# Temp_and_Humi_SHTC3.net
KiCad netlist of a schematic drawn in Altium Designer
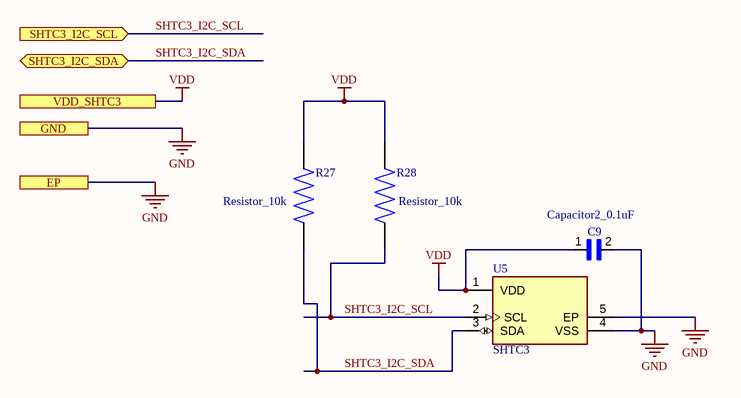
[diagram p0: Temp_and_Humi_SHTC3.SchDoc]

(export (version "E")
  (design (tool "Eeschema 10.0.6"))
  (components
    (comp (ref "C9")
      (value "Capacitor2_0.1uF")
      (footprint "Capacitor2_0.1uF")
      (description "Cap Ceramic 0.1uF 16V X5R 10% SMD 0402 85°C Paper T/R")
      (fields
        (field (name "MANUFACTURER") "KEMET")
        (field (name "MANUFACTURER PART NUMBER") "C0402C104K4PACTU")
      )
      (libsource (lib "Schematic_Lib") (part "Capacitor2_0.1uF"))
    )
    (comp (ref "R27")
      (value "Resistor_10k")
      (footprint "Resistor_10k")
      (description "Res Thin Film 0805 10K Ohm 1% 1/10W ±50ppm/°C Molded SMD SMD Paper T/R")
      (fields
        (field (name "MANUFACTURER") "TE Connectivity Neohm")
        (field (name "MANUFACTURER PART NUMBER") "CPF0805F10KC1")
      )
      (libsource (lib "Schematic_Lib") (part "Resistor_10k"))
    )
    (comp (ref "R28")
      (value "Resistor_10k")
      (footprint "Resistor_10k")
      (description "Res Thin Film 0805 10K Ohm 1% 1/10W ±50ppm/°C Molded SMD SMD Paper T/R")
      (fields
        (field (name "MANUFACTURER") "TE Connectivity Neohm")
        (field (name "MANUFACTURER PART NUMBER") "CPF0805F10KC1")
      )
      (libsource (lib "Schematic_Lib") (part "Resistor_10k"))
    )
    (comp (ref "U5")
      (value "SHTC3")
      (footprint "FP-SHTC3-MFG")
      (description "SENSOR HUMI/TEMP I2C 2% SMD")
      (fields
        (field (name "MANUFACTURER") "Sensirion")
        (field (name "OCTOPART") "https://octopart.com/shtc3-sensirion-91912225")
      )
      (libsource (lib "Altium Content Vault") (part "92e21da4ceb1e434b50171ab113565b"))
    )
  )
  (nets
    (net (code "1") (name "/SHTC3_I2C_SCL") (class "Default")
      (node (ref "R28") (pin "1") (pinfunction "1_1") (pintype "passive"))
      (node (ref "U5") (pin "2") (pinfunction "SCL_2") (pintype "input"))
    )
    (net (code "2") (name "/SHTC3_I2C_SDA") (class "Default")
      (node (ref "R27") (pin "1") (pinfunction "1_1") (pintype "passive"))
      (node (ref "U5") (pin "3") (pinfunction "SDA_3") (pintype "bidirectional"))
    )
    (net (code "3") (name "GND") (class "Default")
      (node (ref "C9") (pin "2") (pinfunction "2_2") (pintype "passive"))
      (node (ref "U5") (pin "4") (pinfunction "VSS_4") (pintype "power_in"))
      (node (ref "U5") (pin "5") (pinfunction "EP_5") (pintype "power_in"))
    )
    (net (code "4") (name "VDD") (class "Default")
      (node (ref "C9") (pin "1") (pinfunction "1_1") (pintype "passive"))
      (node (ref "R27") (pin "2") (pinfunction "2_2") (pintype "passive"))
      (node (ref "R28") (pin "2") (pinfunction "2_2") (pintype "passive"))
      (node (ref "U5") (pin "1") (pinfunction "VDD_1") (pintype "power_in"))
    )
  )
)
